# RGB_1_1.net
KiCad netlist of a schematic drawn in EAGLE
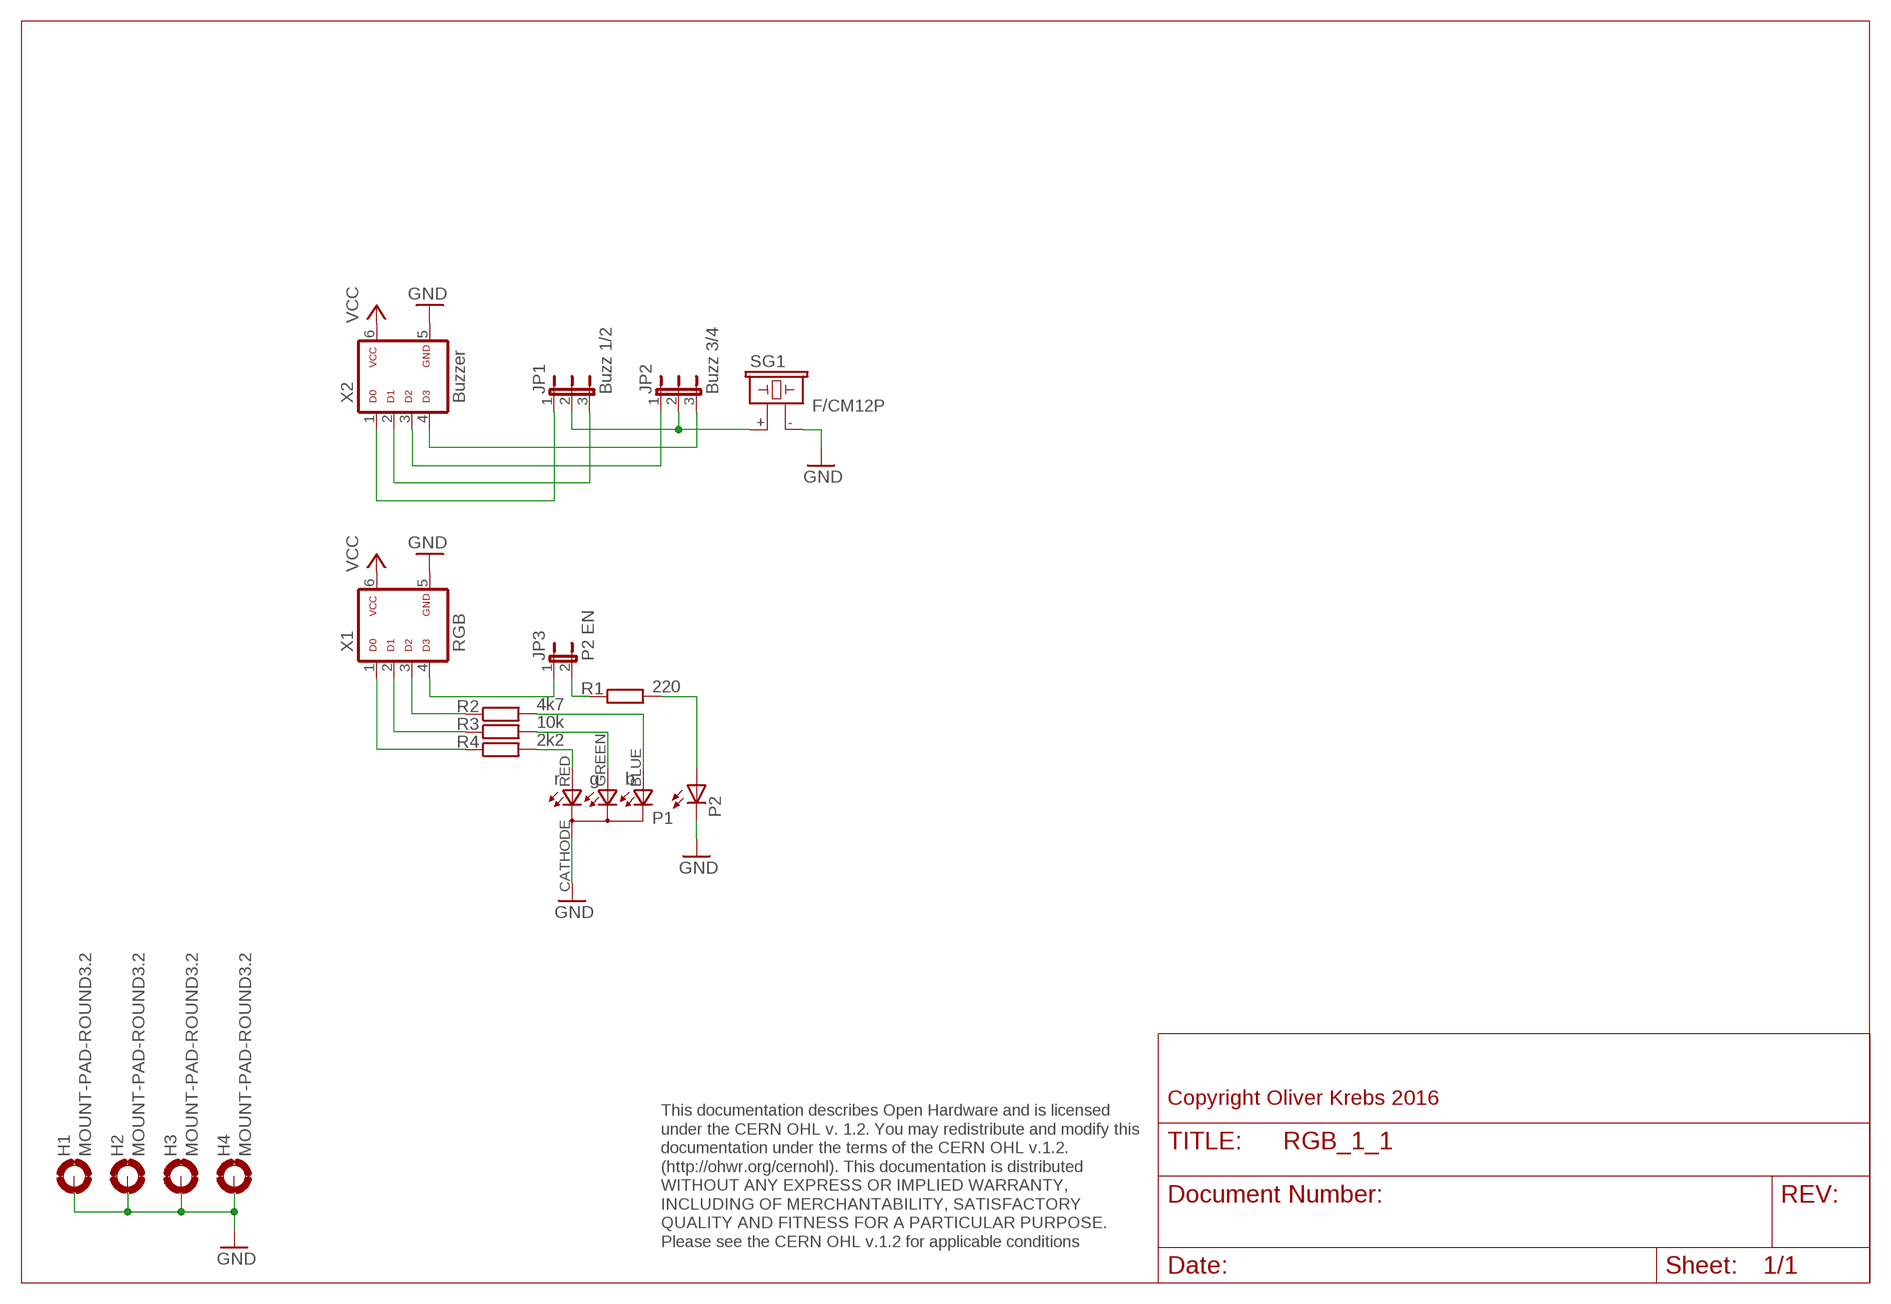
[diagram p0: schematic, sheet 1]

(export (version "E")
  (design (tool "Eeschema 10.0.6"))
  (components
    (comp (ref "H1")
      (value "MOUNT-PAD-ROUND3.2")
      (footprint "eagle-import:3,2-PAD")
      (libsource (lib "eagle-import") (part "MOUNT-PAD-ROUND3.2"))
    )
    (comp (ref "H2")
      (value "MOUNT-PAD-ROUND3.2")
      (footprint "eagle-import:3,2-PAD")
      (libsource (lib "eagle-import") (part "MOUNT-PAD-ROUND3.2"))
    )
    (comp (ref "H3")
      (value "MOUNT-PAD-ROUND3.2")
      (footprint "eagle-import:3,2-PAD")
      (libsource (lib "eagle-import") (part "MOUNT-PAD-ROUND3.2"))
    )
    (comp (ref "H4")
      (value "MOUNT-PAD-ROUND3.2")
      (footprint "eagle-import:3,2-PAD")
      (libsource (lib "eagle-import") (part "MOUNT-PAD-ROUND3.2"))
    )
    (comp (ref "JP1")
      (value "Buzz 1/2")
      (footprint "eagle-import:JP2")
      (libsource (lib "eagle-import") (part "JP2E"))
    )
    (comp (ref "JP2")
      (value "Buzz 3/4")
      (footprint "eagle-import:JP2")
      (libsource (lib "eagle-import") (part "JP2E"))
    )
    (comp (ref "JP3")
      (value "P2 EN")
      (footprint "eagle-import:JP1")
      (libsource (lib "eagle-import") (part "JP1E"))
    )
    (comp (ref "P1")
      (value "RGB-5MM")
      (footprint "eagle-import:RGB5MM")
      (libsource (lib "eagle-import") (part "RGB-5MM"))
    )
    (comp (ref "P2")
      (value "LED5MM")
      (footprint "eagle-import:LED5MM")
      (libsource (lib "eagle-import") (part "LED5MM"))
    )
    (comp (ref "R1")
      (value "220")
      (footprint "eagle-import:0207_10")
      (libsource (lib "eagle-import") (part "R-EU_0207/10"))
    )
    (comp (ref "R2")
      (value "4k7")
      (footprint "eagle-import:0207_10")
      (libsource (lib "eagle-import") (part "R-EU_0207/10"))
    )
    (comp (ref "R3")
      (value "10k")
      (footprint "eagle-import:0207_10")
      (libsource (lib "eagle-import") (part "R-EU_0207/10"))
    )
    (comp (ref "R4")
      (value "2k2")
      (footprint "eagle-import:0207_10")
      (libsource (lib "eagle-import") (part "R-EU_0207/10"))
    )
    (comp (ref "SG1")
      (value "F/CM12P")
      (footprint "eagle-import:F_CM12P")
      (libsource (lib "eagle-import") (part "F/CM12P"))
    )
    (comp (ref "X1")
      (value "RGB")
      (footprint "eagle-import:ML-6")
      (libsource (lib "eagle-import") (part "ML6D"))
    )
    (comp (ref "X2")
      (value "Buzzer")
      (footprint "eagle-import:ML-6")
      (libsource (lib "eagle-import") (part "ML6D"))
    )
  )
  (nets
    (net (code "1") (name "GND") (class "Default")
      (node (ref "H1") (pin "B3,2") (pinfunction "MOUNT_B3,2") (pintype "passive"))
      (node (ref "H2") (pin "B3,2") (pinfunction "MOUNT_B3,2") (pintype "passive"))
      (node (ref "H3") (pin "B3,2") (pinfunction "MOUNT_B3,2") (pintype "passive"))
      (node (ref "H4") (pin "B3,2") (pinfunction "MOUNT_B3,2") (pintype "passive"))
      (node (ref "P1") (pin "CATHODE") (pinfunction "CATHODE_CATHODE") (pintype "passive"))
      (node (ref "P2") (pin "K") (pinfunction "C_K") (pintype "passive"))
      (node (ref "SG1") (pin "-") (pinfunction "2_-") (pintype "passive"))
      (node (ref "X1") (pin "5") (pinfunction "5_5") (pintype "passive"))
      (node (ref "X2") (pin "5") (pinfunction "5_5") (pintype "passive"))
    )
    (net (code "2") (name "Net-(JP1-Pad1)") (class "Default")
      (node (ref "JP1") (pin "1") (pinfunction "1_1") (pintype "passive"))
      (node (ref "X2") (pin "1") (pinfunction "1_1") (pintype "passive"))
    )
    (net (code "3") (name "Net-(JP1-Pad3)") (class "Default")
      (node (ref "JP1") (pin "3") (pinfunction "3_3") (pintype "passive"))
      (node (ref "X2") (pin "2") (pinfunction "2_2") (pintype "passive"))
    )
    (net (code "4") (name "Net-(JP2-Pad1)") (class "Default")
      (node (ref "JP2") (pin "1") (pinfunction "1_1") (pintype "passive"))
      (node (ref "X2") (pin "3") (pinfunction "3_3") (pintype "passive"))
    )
    (net (code "5") (name "Net-(JP2-Pad3)") (class "Default")
      (node (ref "JP2") (pin "3") (pinfunction "3_3") (pintype "passive"))
      (node (ref "X2") (pin "4") (pinfunction "4_4") (pintype "passive"))
    )
    (net (code "6") (name "Net-(JP3-Pad1)") (class "Default")
      (node (ref "JP3") (pin "1") (pinfunction "1_1") (pintype "passive"))
      (node (ref "X1") (pin "4") (pinfunction "4_4") (pintype "passive"))
    )
    (net (code "7") (name "Net-(JP3-Pad2)") (class "Default")
      (node (ref "JP3") (pin "2") (pinfunction "2_2") (pintype "passive"))
      (node (ref "R1") (pin "1") (pinfunction "1_1") (pintype "passive"))
    )
    (net (code "8") (name "Net-(P1-A-BLUE)") (class "Default")
      (node (ref "P1") (pin "BLUE") (pinfunction "A-BLUE_BLUE") (pintype "passive"))
      (node (ref "R2") (pin "2") (pinfunction "2_2") (pintype "passive"))
    )
    (net (code "9") (name "Net-(P1-A-GREEN)") (class "Default")
      (node (ref "P1") (pin "GREEN") (pinfunction "A-GREEN_GREEN") (pintype "passive"))
      (node (ref "R3") (pin "2") (pinfunction "2_2") (pintype "passive"))
    )
    (net (code "10") (name "Net-(P1-A-RED)") (class "Default")
      (node (ref "P1") (pin "RED") (pinfunction "A-RED_RED") (pintype "passive"))
      (node (ref "R4") (pin "2") (pinfunction "2_2") (pintype "passive"))
    )
    (net (code "11") (name "Net-(P2-PadA)") (class "Default")
      (node (ref "P2") (pin "A") (pinfunction "A_A") (pintype "passive"))
      (node (ref "R1") (pin "2") (pinfunction "2_2") (pintype "passive"))
    )
    (net (code "12") (name "Net-(R2-Pad1)") (class "Default")
      (node (ref "R2") (pin "1") (pinfunction "1_1") (pintype "passive"))
      (node (ref "X1") (pin "3") (pinfunction "3_3") (pintype "passive"))
    )
    (net (code "13") (name "Net-(R3-Pad1)") (class "Default")
      (node (ref "R3") (pin "1") (pinfunction "1_1") (pintype "passive"))
      (node (ref "X1") (pin "2") (pinfunction "2_2") (pintype "passive"))
    )
    (net (code "14") (name "Net-(R4-Pad1)") (class "Default")
      (node (ref "R4") (pin "1") (pinfunction "1_1") (pintype "passive"))
      (node (ref "X1") (pin "1") (pinfunction "1_1") (pintype "passive"))
    )
    (net (code "15") (name "Net-(SG1-1)") (class "Default")
      (node (ref "JP1") (pin "2") (pinfunction "2_2") (pintype "passive"))
      (node (ref "JP2") (pin "2") (pinfunction "2_2") (pintype "passive"))
      (node (ref "SG1") (pin "+") (pinfunction "1_+") (pintype "passive"))
    )
    (net (code "16") (name "VCC") (class "Default")
      (node (ref "X1") (pin "6") (pinfunction "6_6") (pintype "passive"))
      (node (ref "X2") (pin "6") (pinfunction "6_6") (pintype "passive"))
    )
  )
)
